# AfternoonCape_RevA2_ADImux.net
KiCad netlist of a schematic drawn in Altium Designer
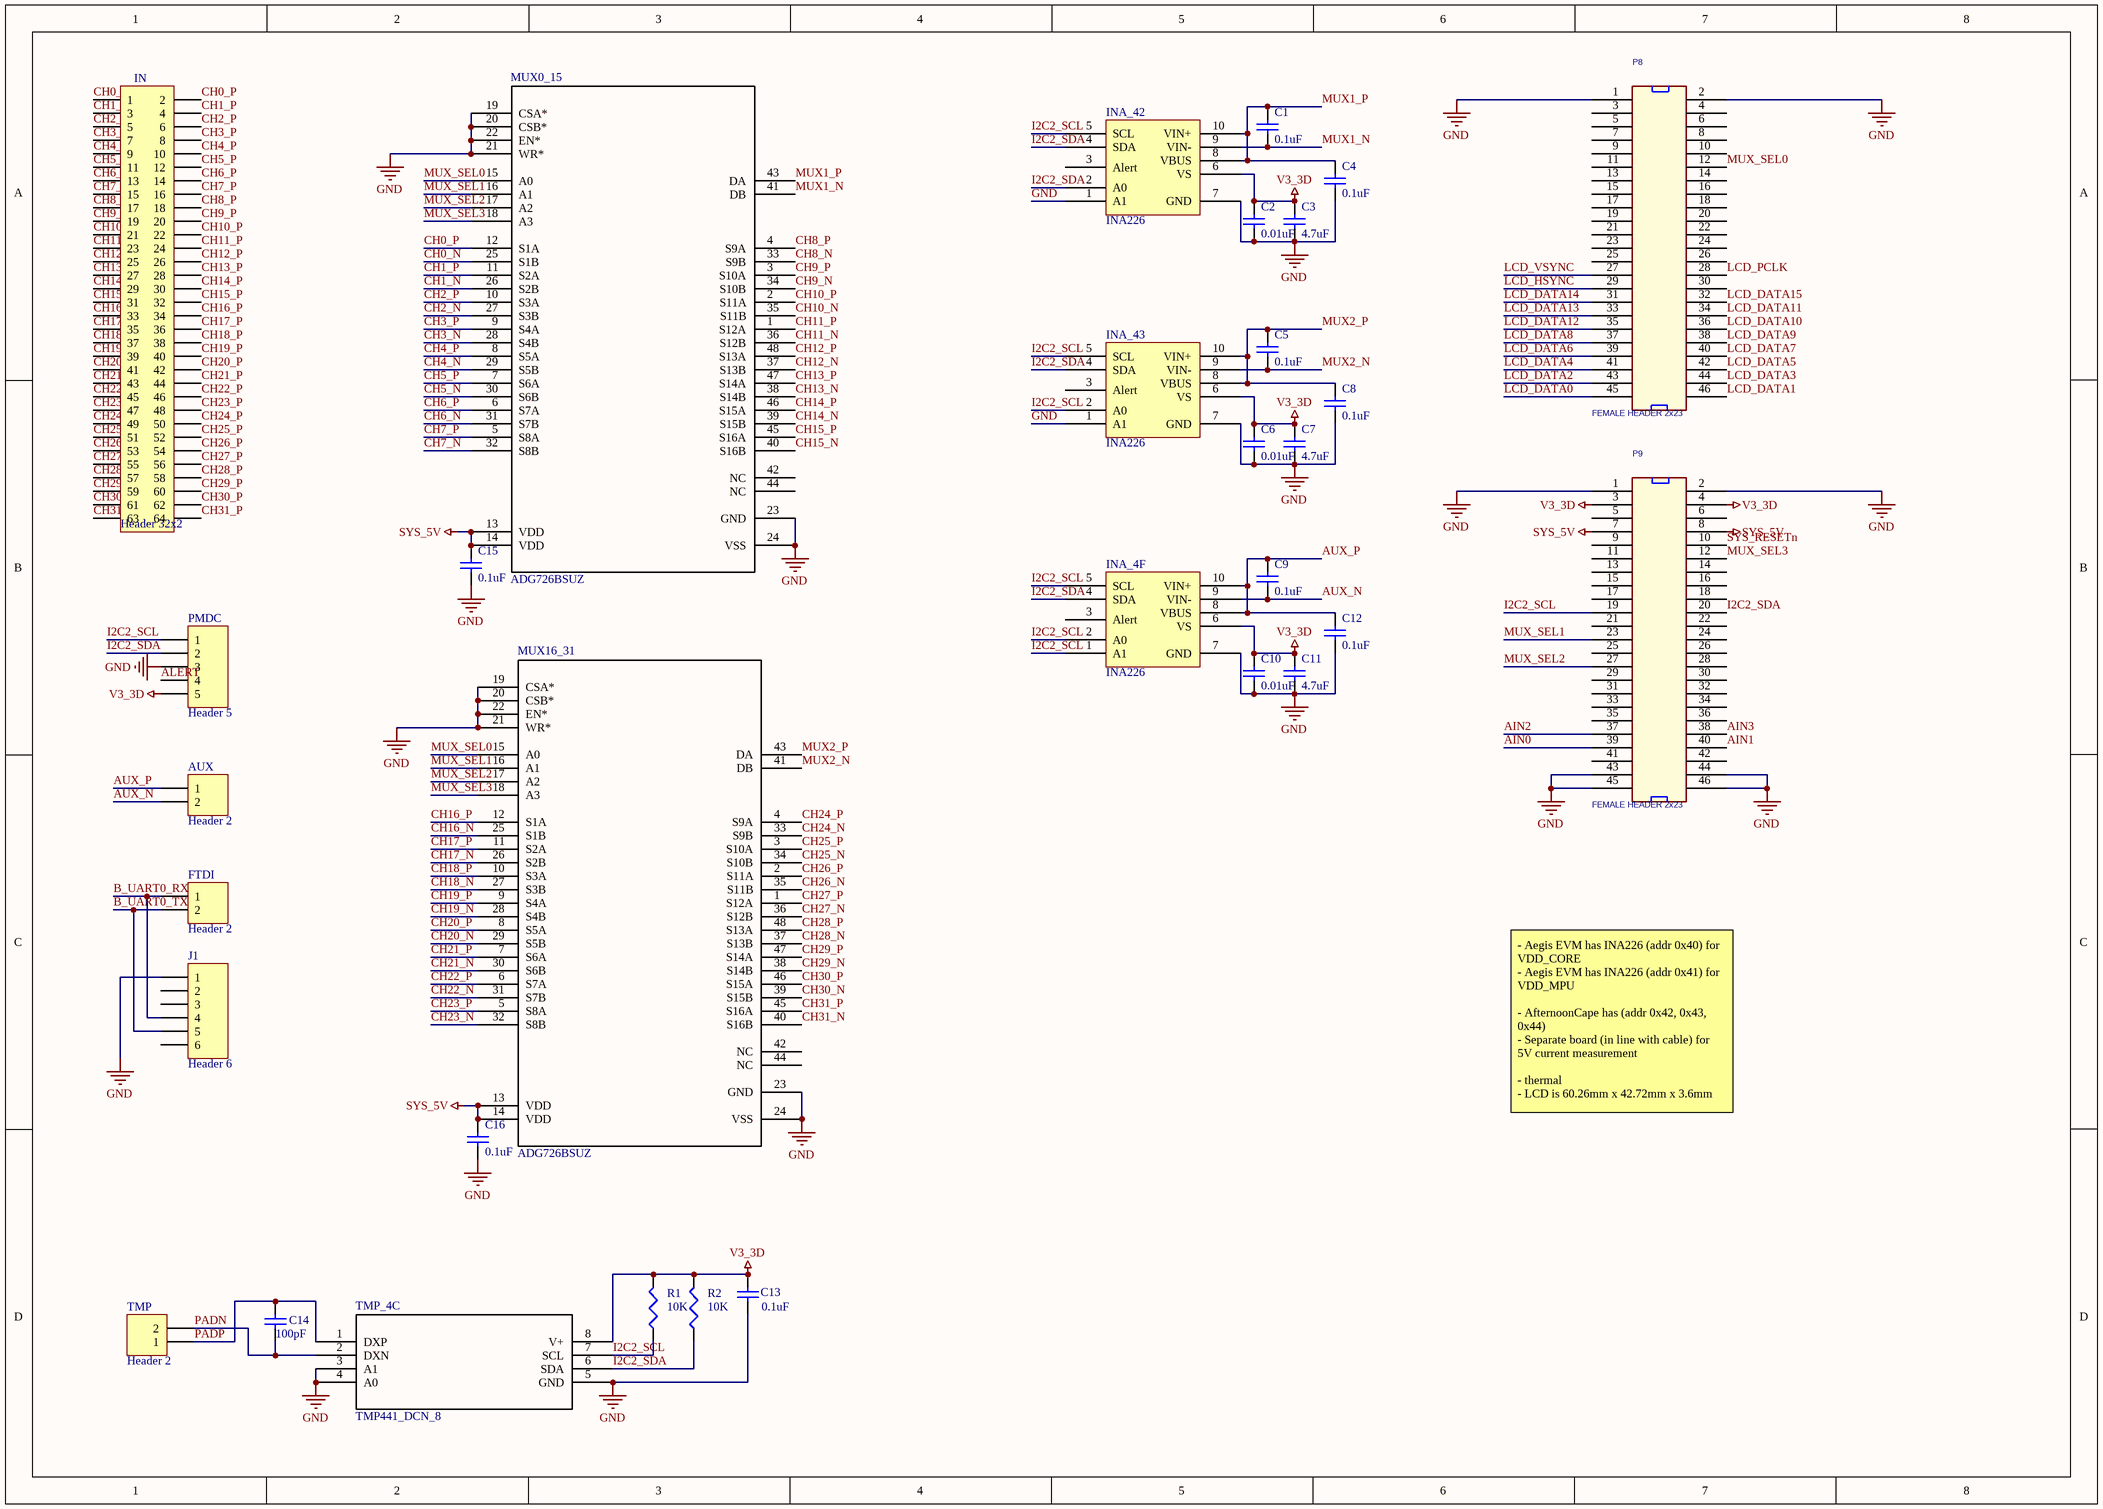
[diagram p0: AfternoonCape_RevA2_ADImux.SchDoc]

(export (version "E")
  (design (tool "Eeschema 10.0.6"))
  (components
    (comp (ref "AUX")
      (value "Header 2")
      (footprint "HDR1X2")
      (description "Header, 2-Pin")
      (fields (field (name "PUBLISHER") "Altium Limited"))
      (libsource (lib "Miscellaneous Connectors") (part "Header 2"))
    )
    (comp (ref "C1")
      (value "0.1uF")
      (footprint "0402")
      (description "Capacitor (Semiconductor SIM Model)")
      (fields (field (name "Comment") "Cap Semi") (field (name "PUBLISHER") "Altium Limited"))
      (libsource (lib "Miscellaneous Devices") (part "Cap Semi"))
    )
    (comp (ref "C2")
      (value "0.01uF")
      (footprint "0402")
      (description "Capacitor (Semiconductor SIM Model)")
      (fields (field (name "Comment") "Cap Semi") (field (name "PUBLISHER") "Altium Limited"))
      (libsource (lib "Miscellaneous Devices") (part "Cap Semi"))
    )
    (comp (ref "C3")
      (value "4.7uF")
      (footprint "0402")
      (description "Capacitor (Semiconductor SIM Model)")
      (fields (field (name "Comment") "Cap Semi") (field (name "PUBLISHER") "Altium Limited"))
      (libsource (lib "Miscellaneous Devices") (part "Cap Semi"))
    )
    (comp (ref "C4")
      (value "0.1uF")
      (footprint "0402")
      (description "Capacitor (Semiconductor SIM Model)")
      (fields (field (name "Comment") "Cap Semi") (field (name "PUBLISHER") "Altium Limited"))
      (libsource (lib "Miscellaneous Devices") (part "Cap Semi"))
    )
    (comp (ref "C5")
      (value "0.1uF")
      (footprint "0402")
      (description "Capacitor (Semiconductor SIM Model)")
      (fields (field (name "Comment") "Cap Semi") (field (name "PUBLISHER") "Altium Limited"))
      (libsource (lib "Miscellaneous Devices") (part "Cap Semi"))
    )
    (comp (ref "C6")
      (value "0.01uF")
      (footprint "0402")
      (description "Capacitor (Semiconductor SIM Model)")
      (fields (field (name "Comment") "Cap Semi") (field (name "PUBLISHER") "Altium Limited"))
      (libsource (lib "Miscellaneous Devices") (part "Cap Semi"))
    )
    (comp (ref "C7")
      (value "4.7uF")
      (footprint "0402")
      (description "Capacitor (Semiconductor SIM Model)")
      (fields (field (name "Comment") "Cap Semi") (field (name "PUBLISHER") "Altium Limited"))
      (libsource (lib "Miscellaneous Devices") (part "Cap Semi"))
    )
    (comp (ref "C8")
      (value "0.1uF")
      (footprint "0402")
      (description "Capacitor (Semiconductor SIM Model)")
      (fields (field (name "Comment") "Cap Semi") (field (name "PUBLISHER") "Altium Limited"))
      (libsource (lib "Miscellaneous Devices") (part "Cap Semi"))
    )
    (comp (ref "C9")
      (value "0.1uF")
      (footprint "0402")
      (description "Capacitor (Semiconductor SIM Model)")
      (fields (field (name "Comment") "Cap Semi") (field (name "PUBLISHER") "Altium Limited"))
      (libsource (lib "Miscellaneous Devices") (part "Cap Semi"))
    )
    (comp (ref "C10")
      (value "0.01uF")
      (footprint "0402")
      (description "Capacitor (Semiconductor SIM Model)")
      (fields (field (name "Comment") "Cap Semi") (field (name "PUBLISHER") "Altium Limited"))
      (libsource (lib "Miscellaneous Devices") (part "Cap Semi"))
    )
    (comp (ref "C11")
      (value "4.7uF")
      (footprint "0402")
      (description "Capacitor (Semiconductor SIM Model)")
      (fields (field (name "Comment") "Cap Semi") (field (name "PUBLISHER") "Altium Limited"))
      (libsource (lib "Miscellaneous Devices") (part "Cap Semi"))
    )
    (comp (ref "C12")
      (value "0.1uF")
      (footprint "0402")
      (description "Capacitor (Semiconductor SIM Model)")
      (fields (field (name "Comment") "Cap Semi") (field (name "PUBLISHER") "Altium Limited"))
      (libsource (lib "Miscellaneous Devices") (part "Cap Semi"))
    )
    (comp (ref "C13")
      (value "0.1uF")
      (footprint "0402")
      (description "Capacitor (Semiconductor SIM Model)")
      (fields (field (name "Comment") "Cap Semi") (field (name "PUBLISHER") "Altium Limited"))
      (libsource (lib "Miscellaneous Devices") (part "Cap Semi"))
    )
    (comp (ref "C14")
      (value "100pF")
      (footprint "0402")
      (description "Capacitor (Semiconductor SIM Model)")
      (fields (field (name "Comment") "Cap Semi") (field (name "PUBLISHER") "Altium Limited"))
      (libsource (lib "Miscellaneous Devices") (part "Cap Semi"))
    )
    (comp (ref "C15")
      (value "0.1uF")
      (footprint "0402")
      (description "Capacitor (Semiconductor SIM Model)")
      (fields (field (name "Comment") "Cap Semi") (field (name "PUBLISHER") "Altium Limited"))
      (libsource (lib "Miscellaneous Devices") (part "Cap Semi"))
    )
    (comp (ref "C16")
      (value "0.1uF")
      (footprint "0402")
      (description "Capacitor (Semiconductor SIM Model)")
      (fields (field (name "Comment") "Cap Semi") (field (name "PUBLISHER") "Altium Limited"))
      (libsource (lib "Miscellaneous Devices") (part "Cap Semi"))
    )
    (comp (ref "FTDI")
      (value "Header 2")
      (footprint "HDR1X2")
      (description "Header, 2-Pin")
      (fields (field (name "PUBLISHER") "Altium Limited"))
      (libsource (lib "Miscellaneous Connectors") (part "Header 2"))
    )
    (comp (ref "IN")
      (value "Header 32x2")
      (footprint "HDR2x32")
      (description "Header, 32-Pin, Dual row")
      (libsource (lib "Miscellaneous Connectors") (part "Header 32x2"))
    )
    (comp (ref "INA_4F") (value "INA226") (footprint "DGS10") (libsource (lib "INA226") (part "INA226")))
    (comp (ref "INA_42") (value "INA226") (footprint "DGS10") (libsource (lib "INA226") (part "INA226")))
    (comp (ref "INA_43") (value "INA226") (footprint "DGS10") (libsource (lib "INA226") (part "INA226")))
    (comp (ref "J1")
      (value "Header 6")
      (footprint "HDR1X6")
      (description "6-pin female header, long legs for FTDI-USB cable")
      (fields (field (name "PUBLISHER") "Altium Limited"))
      (libsource (lib "Miscellaneous Connectors") (part "Header 6"))
    )
    (comp (ref "MUX0_15")
      (value "ADG726BSUZ")
      (footprint "SU_48")
      (description "Imported")
      (libsource (lib "ADG726_ADG732") (part "ADG726BSUZ"))
    )
    (comp (ref "MUX16_31")
      (value "ADG726BSUZ")
      (footprint "SU_48")
      (description "Imported")
      (libsource (lib "ADG726_ADG732") (part "ADG726BSUZ"))
    )
    (comp (ref "P8")
      (value "FEMALE HEADER 2x23")
      (description "CONN HEADER FMAL 46PS.1\" DL GOLD")
      (fields
        (field (name "MANUFACTURER") "Sullins Connector Solutions")
        (field (name "MANUFACTURER PART NUMBER") "PPPC232LFBN-RC")
      )
      (libsource (lib "BEAGLEBONEBLACK_REV A5B") (part "HDR_46_F_2_0.1_0.1"))
    )
    (comp (ref "P9")
      (value "FEMALE HEADER 2x23")
      (description "CONN HEADER FMAL 46PS.1\" DL GOLD")
      (fields
        (field (name "MANUFACTURER") "Sullins Connector Solutions")
        (field (name "MANUFACTURER PART NUMBER") "PPPC232LFBN-RC")
      )
      (libsource (lib "BEAGLEBONEBLACK_REV A5B") (part "HDR_46_F_2_0.1_0.1"))
    )
    (comp (ref "PMDC")
      (value "Header 5")
      (footprint "HDR1X5")
      (description "Header, 5-Pin")
      (fields (field (name "PUBLISHER") "Altium Limited"))
      (libsource (lib "Miscellaneous Connectors") (part "Header 5"))
    )
    (comp (ref "R1")
      (value "10K")
      (footprint "0402")
      (description "Resistor")
      (fields (field (name "Comment") "Res3") (field (name "PUBLISHER") "Altium Limited"))
      (libsource (lib "Miscellaneous Devices") (part "Res3"))
    )
    (comp (ref "R2")
      (value "10K")
      (footprint "0402")
      (description "Resistor")
      (fields (field (name "Comment") "Res3") (field (name "PUBLISHER") "Altium Limited"))
      (libsource (lib "Miscellaneous Devices") (part "Res3"))
    )
    (comp (ref "TMP")
      (value "Header 2")
      (footprint "HDR1X2")
      (description "Header, 2-Pin")
      (fields (field (name "PUBLISHER") "Altium Limited"))
      (libsource (lib "") (part "Header 2_1"))
    )
    (comp (ref "TMP_4C")
      (value "TMP441_DCN_8")
      (footprint "TMP441:DCN8-L")
      (description "Imported")
      (fields
        (field (name "MANUFACTURER_PART_NUMBER") "tmp441_dcn_8")
        (field (name "GENERIC_PART_NUMBER") "TMP441")
      )
      (libsource (lib "TMP441") (part "TMP441_DCN_8"))
    )
  )
  (nets
    (net (code "1") (name "/AIN0") (class "Default")
      (node (ref "P9") (pin "39") (pinfunction "20_39") (pintype "passive"))
    )
    (net (code "2") (name "/AIN1") (class "Default")
      (node (ref "P9") (pin "40") (pinfunction "45_40") (pintype "passive"))
    )
    (net (code "3") (name "/AIN2") (class "Default")
      (node (ref "P9") (pin "37") (pinfunction "19_37") (pintype "passive"))
    )
    (net (code "4") (name "/AIN3") (class "Default")
      (node (ref "P9") (pin "38") (pinfunction "44_38") (pintype "passive"))
    )
    (net (code "5") (name "/ALERT") (class "Default")
      (node (ref "PMDC") (pin "4") (pinfunction "4_4") (pintype "passive"))
    )
    (net (code "6") (name "/AUX_N") (class "Default")
      (node (ref "AUX") (pin "2") (pinfunction "2_2") (pintype "passive"))
      (node (ref "C9") (pin "1") (pinfunction "1_1") (pintype "passive"))
      (node (ref "INA_4F") (pin "9") (pinfunction "VIN-_9") (pintype "passive"))
    )
    (net (code "7") (name "/AUX_P") (class "Default")
      (node (ref "AUX") (pin "1") (pinfunction "1_1") (pintype "passive"))
      (node (ref "C12") (pin "2") (pinfunction "2_2") (pintype "passive"))
      (node (ref "C9") (pin "2") (pinfunction "2_2") (pintype "passive"))
      (node (ref "INA_4F") (pin "10") (pinfunction "VIN+_10") (pintype "passive"))
      (node (ref "INA_4F") (pin "8") (pinfunction "VBUS_8") (pintype "passive"))
    )
    (net (code "8") (name "/B_UART0_RX") (class "Default")
      (node (ref "FTDI") (pin "1") (pinfunction "1_1") (pintype "passive"))
      (node (ref "J1") (pin "4") (pinfunction "4_4") (pintype "passive"))
    )
    (net (code "9") (name "/B_UART0_TX") (class "Default")
      (node (ref "FTDI") (pin "2") (pinfunction "2_2") (pintype "passive"))
      (node (ref "J1") (pin "5") (pinfunction "5_5") (pintype "passive"))
    )
    (net (code "10") (name "/CH0_N") (class "Default")
      (node (ref "IN") (pin "1") (pinfunction "1_1") (pintype "passive"))
      (node (ref "MUX0_15") (pin "25") (pinfunction "S1B_25") (pintype "passive"))
    )
    (net (code "11") (name "/CH0_P") (class "Default")
      (node (ref "IN") (pin "2") (pinfunction "2_2") (pintype "passive"))
      (node (ref "MUX0_15") (pin "12") (pinfunction "S1A_12") (pintype "passive"))
    )
    (net (code "12") (name "/CH1_N") (class "Default")
      (node (ref "IN") (pin "3") (pinfunction "3_3") (pintype "passive"))
      (node (ref "MUX0_15") (pin "26") (pinfunction "S2B_26") (pintype "passive"))
    )
    (net (code "13") (name "/CH1_P") (class "Default")
      (node (ref "IN") (pin "4") (pinfunction "4_4") (pintype "passive"))
      (node (ref "MUX0_15") (pin "11") (pinfunction "S2A_11") (pintype "passive"))
    )
    (net (code "14") (name "/CH2_N") (class "Default")
      (node (ref "IN") (pin "5") (pinfunction "5_5") (pintype "passive"))
      (node (ref "MUX0_15") (pin "27") (pinfunction "S3B_27") (pintype "passive"))
    )
    (net (code "15") (name "/CH2_P") (class "Default")
      (node (ref "IN") (pin "6") (pinfunction "6_6") (pintype "passive"))
      (node (ref "MUX0_15") (pin "10") (pinfunction "S3A_10") (pintype "passive"))
    )
    (net (code "16") (name "/CH3_N") (class "Default")
      (node (ref "IN") (pin "7") (pinfunction "7_7") (pintype "passive"))
      (node (ref "MUX0_15") (pin "28") (pinfunction "S4B_28") (pintype "passive"))
    )
    (net (code "17") (name "/CH3_P") (class "Default")
      (node (ref "IN") (pin "8") (pinfunction "8_8") (pintype "passive"))
      (node (ref "MUX0_15") (pin "9") (pinfunction "S4A_9") (pintype "passive"))
    )
    (net (code "18") (name "/CH4_N") (class "Default")
      (node (ref "IN") (pin "9") (pinfunction "9_9") (pintype "passive"))
      (node (ref "MUX0_15") (pin "29") (pinfunction "S5B_29") (pintype "passive"))
    )
    (net (code "19") (name "/CH4_P") (class "Default")
      (node (ref "IN") (pin "10") (pinfunction "10_10") (pintype "passive"))
      (node (ref "MUX0_15") (pin "8") (pinfunction "S5A_8") (pintype "passive"))
    )
    (net (code "20") (name "/CH5_N") (class "Default")
      (node (ref "IN") (pin "11") (pinfunction "11_11") (pintype "passive"))
      (node (ref "MUX0_15") (pin "30") (pinfunction "S6B_30") (pintype "passive"))
    )
    (net (code "21") (name "/CH5_P") (class "Default")
      (node (ref "IN") (pin "12") (pinfunction "12_12") (pintype "passive"))
      (node (ref "MUX0_15") (pin "7") (pinfunction "S6A_7") (pintype "passive"))
    )
    (net (code "22") (name "/CH6_N") (class "Default")
      (node (ref "IN") (pin "13") (pinfunction "13_13") (pintype "passive"))
      (node (ref "MUX0_15") (pin "31") (pinfunction "S7B_31") (pintype "passive"))
    )
    (net (code "23") (name "/CH6_P") (class "Default")
      (node (ref "IN") (pin "14") (pinfunction "14_14") (pintype "passive"))
      (node (ref "MUX0_15") (pin "6") (pinfunction "S7A_6") (pintype "passive"))
    )
    (net (code "24") (name "/CH7_N") (class "Default")
      (node (ref "IN") (pin "15") (pinfunction "15_15") (pintype "passive"))
      (node (ref "MUX0_15") (pin "32") (pinfunction "S8B_32") (pintype "passive"))
    )
    (net (code "25") (name "/CH7_P") (class "Default")
      (node (ref "IN") (pin "16") (pinfunction "16_16") (pintype "passive"))
      (node (ref "MUX0_15") (pin "5") (pinfunction "S8A_5") (pintype "passive"))
    )
    (net (code "26") (name "/CH8_N") (class "Default")
      (node (ref "IN") (pin "17") (pinfunction "17_17") (pintype "passive"))
      (node (ref "MUX0_15") (pin "33") (pinfunction "S9B_33") (pintype "passive"))
    )
    (net (code "27") (name "/CH8_P") (class "Default")
      (node (ref "IN") (pin "18") (pinfunction "18_18") (pintype "passive"))
      (node (ref "MUX0_15") (pin "4") (pinfunction "S9A_4") (pintype "passive"))
    )
    (net (code "28") (name "/CH9_N") (class "Default")
      (node (ref "IN") (pin "19") (pinfunction "19_19") (pintype "passive"))
      (node (ref "MUX0_15") (pin "34") (pinfunction "S10B_34") (pintype "passive"))
    )
    (net (code "29") (name "/CH9_P") (class "Default")
      (node (ref "IN") (pin "20") (pinfunction "20_20") (pintype "passive"))
      (node (ref "MUX0_15") (pin "3") (pinfunction "S10A_3") (pintype "passive"))
    )
    (net (code "30") (name "/CH10_N") (class "Default")
      (node (ref "IN") (pin "21") (pinfunction "21_21") (pintype "passive"))
      (node (ref "MUX0_15") (pin "35") (pinfunction "S11B_35") (pintype "passive"))
    )
    (net (code "31") (name "/CH10_P") (class "Default")
      (node (ref "IN") (pin "22") (pinfunction "22_22") (pintype "passive"))
      (node (ref "MUX0_15") (pin "2") (pinfunction "S11A_2") (pintype "passive"))
    )
    (net (code "32") (name "/CH11_N") (class "Default")
      (node (ref "IN") (pin "23") (pinfunction "23_23") (pintype "passive"))
      (node (ref "MUX0_15") (pin "36") (pinfunction "S12B_36") (pintype "passive"))
    )
    (net (code "33") (name "/CH11_P") (class "Default")
      (node (ref "IN") (pin "24") (pinfunction "24_24") (pintype "passive"))
      (node (ref "MUX0_15") (pin "1") (pinfunction "S12A_1") (pintype "passive"))
    )
    (net (code "34") (name "/CH12_N") (class "Default")
      (node (ref "IN") (pin "25") (pinfunction "25_25") (pintype "passive"))
      (node (ref "MUX0_15") (pin "37") (pinfunction "S13B_37") (pintype "passive"))
    )
    (net (code "35") (name "/CH12_P") (class "Default")
      (node (ref "IN") (pin "26") (pinfunction "26_26") (pintype "passive"))
      (node (ref "MUX0_15") (pin "48") (pinfunction "S13A_48") (pintype "passive"))
    )
    (net (code "36") (name "/CH13_N") (class "Default")
      (node (ref "IN") (pin "27") (pinfunction "27_27") (pintype "passive"))
      (node (ref "MUX0_15") (pin "38") (pinfunction "S14B_38") (pintype "passive"))
    )
    (net (code "37") (name "/CH13_P") (class "Default")
      (node (ref "IN") (pin "28") (pinfunction "28_28") (pintype "passive"))
      (node (ref "MUX0_15") (pin "47") (pinfunction "S14A_47") (pintype "passive"))
    )
    (net (code "38") (name "/CH14_N") (class "Default")
      (node (ref "IN") (pin "29") (pinfunction "29_29") (pintype "passive"))
      (node (ref "MUX0_15") (pin "39") (pinfunction "S15B_39") (pintype "passive"))
    )
    (net (code "39") (name "/CH14_P") (class "Default")
      (node (ref "IN") (pin "30") (pinfunction "30_30") (pintype "passive"))
      (node (ref "MUX0_15") (pin "46") (pinfunction "S15A_46") (pintype "passive"))
    )
    (net (code "40") (name "/CH15_N") (class "Default")
      (node (ref "IN") (pin "31") (pinfunction "31_31") (pintype "passive"))
      (node (ref "MUX0_15") (pin "40") (pinfunction "S16B_40") (pintype "passive"))
    )
    (net (code "41") (name "/CH15_P") (class "Default")
      (node (ref "IN") (pin "32") (pinfunction "32_32") (pintype "passive"))
      (node (ref "MUX0_15") (pin "45") (pinfunction "S16A_45") (pintype "passive"))
    )
    (net (code "42") (name "/CH16_N") (class "Default")
      (node (ref "IN") (pin "33") (pinfunction "33_33") (pintype "passive"))
      (node (ref "MUX16_31") (pin "25") (pinfunction "S1B_25") (pintype "passive"))
    )
    (net (code "43") (name "/CH16_P") (class "Default")
      (node (ref "IN") (pin "34") (pinfunction "34_34") (pintype "passive"))
      (node (ref "MUX16_31") (pin "12") (pinfunction "S1A_12") (pintype "passive"))
    )
    (net (code "44") (name "/CH17_N") (class "Default")
      (node (ref "IN") (pin "35") (pinfunction "35_35") (pintype "passive"))
      (node (ref "MUX16_31") (pin "26") (pinfunction "S2B_26") (pintype "passive"))
    )
    (net (code "45") (name "/CH17_P") (class "Default")
      (node (ref "IN") (pin "36") (pinfunction "36_36") (pintype "passive"))
      (node (ref "MUX16_31") (pin "11") (pinfunction "S2A_11") (pintype "passive"))
    )
    (net (code "46") (name "/CH18_N") (class "Default")
      (node (ref "IN") (pin "37") (pinfunction "37_37") (pintype "passive"))
      (node (ref "MUX16_31") (pin "27") (pinfunction "S3B_27") (pintype "passive"))
    )
    (net (code "47") (name "/CH18_P") (class "Default")
      (node (ref "IN") (pin "38") (pinfunction "38_38") (pintype "passive"))
      (node (ref "MUX16_31") (pin "10") (pinfunction "S3A_10") (pintype "passive"))
    )
    (net (code "48") (name "/CH19_N") (class "Default")
      (node (ref "IN") (pin "39") (pinfunction "39_39") (pintype "passive"))
      (node (ref "MUX16_31") (pin "28") (pinfunction "S4B_28") (pintype "passive"))
    )
    (net (code "49") (name "/CH19_P") (class "Default")
      (node (ref "IN") (pin "40") (pinfunction "40_40") (pintype "passive"))
      (node (ref "MUX16_31") (pin "9") (pinfunction "S4A_9") (pintype "passive"))
    )
    (net (code "50") (name "/CH20_N") (class "Default")
      (node (ref "IN") (pin "41") (pinfunction "41_41") (pintype "passive"))
      (node (ref "MUX16_31") (pin "29") (pinfunction "S5B_29") (pintype "passive"))
    )
    (net (code "51") (name "/CH20_P") (class "Default")
      (node (ref "IN") (pin "42") (pinfunction "42_42") (pintype "passive"))
      (node (ref "MUX16_31") (pin "8") (pinfunction "S5A_8") (pintype "passive"))
    )
    (net (code "52") (name "/CH21_N") (class "Default")
      (node (ref "IN") (pin "43") (pinfunction "43_43") (pintype "passive"))
      (node (ref "MUX16_31") (pin "30") (pinfunction "S6B_30") (pintype "passive"))
    )
    (net (code "53") (name "/CH21_P") (class "Default")
      (node (ref "IN") (pin "44") (pinfunction "44_44") (pintype "passive"))
      (node (ref "MUX16_31") (pin "7") (pinfunction "S6A_7") (pintype "passive"))
    )
    (net (code "54") (name "/CH22_N") (class "Default")
      (node (ref "IN") (pin "45") (pinfunction "45_45") (pintype "passive"))
      (node (ref "MUX16_31") (pin "31") (pinfunction "S7B_31") (pintype "passive"))
    )
    (net (code "55") (name "/CH22_P") (class "Default")
      (node (ref "IN") (pin "46") (pinfunction "46_46") (pintype "passive"))
      (node (ref "MUX16_31") (pin "6") (pinfunction "S7A_6") (pintype "passive"))
    )
    (net (code "56") (name "/CH23_N") (class "Default")
      (node (ref "IN") (pin "47") (pinfunction "47_47") (pintype "passive"))
      (node (ref "MUX16_31") (pin "32") (pinfunction "S8B_32") (pintype "passive"))
    )
    (net (code "57") (name "/CH23_P") (class "Default")
      (node (ref "IN") (pin "48") (pinfunction "48_48") (pintype "passive"))
      (node (ref "MUX16_31") (pin "5") (pinfunction "S8A_5") (pintype "passive"))
    )
    (net (code "58") (name "/CH24_N") (class "Default")
      (node (ref "IN") (pin "49") (pinfunction "49_49") (pintype "passive"))
      (node (ref "MUX16_31") (pin "33") (pinfunction "S9B_33") (pintype "passive"))
    )
    (net (code "59") (name "/CH24_P") (class "Default")
      (node (ref "IN") (pin "50") (pinfunction "50_50") (pintype "passive"))
      (node (ref "MUX16_31") (pin "4") (pinfunction "S9A_4") (pintype "passive"))
    )
    (net (code "60") (name "/CH25_N") (class "Default")
      (node (ref "IN") (pin "51") (pinfunction "51_51") (pintype "passive"))
      (node (ref "MUX16_31") (pin "34") (pinfunction "S10B_34") (pintype "passive"))
    )
    (net (code "61") (name "/CH25_P") (class "Default")
      (node (ref "IN") (pin "52") (pinfunction "52_52") (pintype "passive"))
      (node (ref "MUX16_31") (pin "3") (pinfunction "S10A_3") (pintype "passive"))
    )
    (net (code "62") (name "/CH26_N") (class "Default")
      (node (ref "IN") (pin "53") (pinfunction "53_53") (pintype "passive"))
      (node (ref "MUX16_31") (pin "35") (pinfunction "S11B_35") (pintype "passive"))
    )
    (net (code "63") (name "/CH26_P") (class "Default")
      (node (ref "IN") (pin "54") (pinfunction "54_54") (pintype "passive"))
      (node (ref "MUX16_31") (pin "2") (pinfunction "S11A_2") (pintype "passive"))
    )
    (net (code "64") (name "/CH27_N") (class "Default")
      (node (ref "IN") (pin "55") (pinfunction "55_55") (pintype "passive"))
      (node (ref "MUX16_31") (pin "36") (pinfunction "S12B_36") (pintype "passive"))
    )
    (net (code "65") (name "/CH27_P") (class "Default")
      (node (ref "IN") (pin "56") (pinfunction "56_56") (pintype "passive"))
      (node (ref "MUX16_31") (pin "1") (pinfunction "S12A_1") (pintype "passive"))
    )
    (net (code "66") (name "/CH28_N") (class "Default")
      (node (ref "IN") (pin "57") (pinfunction "57_57") (pintype "passive"))
      (node (ref "MUX16_31") (pin "37") (pinfunction "S13B_37") (pintype "passive"))
    )
    (net (code "67") (name "/CH28_P") (class "Default")
      (node (ref "IN") (pin "58") (pinfunction "58_58") (pintype "passive"))
      (node (ref "MUX16_31") (pin "48") (pinfunction "S13A_48") (pintype "passive"))
    )
    (net (code "68") (name "/CH29_N") (class "Default")
      (node (ref "IN") (pin "59") (pinfunction "59_59") (pintype "passive"))
      (node (ref "MUX16_31") (pin "38") (pinfunction "S14B_38") (pintype "passive"))
    )
    (net (code "69") (name "/CH29_P") (class "Default")
      (node (ref "IN") (pin "60") (pinfunction "60_60") (pintype "passive"))
      (node (ref "MUX16_31") (pin "47") (pinfunction "S14A_47") (pintype "passive"))
    )
    (net (code "70") (name "/CH30_N") (class "Default")
      (node (ref "IN") (pin "61") (pinfunction "61_61") (pintype "passive"))
      (node (ref "MUX16_31") (pin "39") (pinfunction "S15B_39") (pintype "passive"))
    )
    (net (code "71") (name "/CH30_P") (class "Default")
      (node (ref "IN") (pin "62") (pinfunction "62_62") (pintype "passive"))
      (node (ref "MUX16_31") (pin "46") (pinfunction "S15A_46") (pintype "passive"))
    )
    (net (code "72") (name "/CH31_N") (class "Default")
      (node (ref "IN") (pin "63") (pinfunction "63_63") (pintype "passive"))
      (node (ref "MUX16_31") (pin "40") (pinfunction "S16B_40") (pintype "passive"))
    )
    (net (code "73") (name "/CH31_P") (class "Default")
      (node (ref "IN") (pin "64") (pinfunction "64_64") (pintype "passive"))
      (node (ref "MUX16_31") (pin "45") (pinfunction "S16A_45") (pintype "passive"))
    )
    (net (code "74") (name "/I2C2_SCL") (class "Default")
      (node (ref "INA_42") (pin "5") (pinfunction "SCL_5") (pintype "passive"))
      (node (ref "INA_43") (pin "2") (pinfunction "A0_2") (pintype "passive"))
      (node (ref "INA_43") (pin "5") (pinfunction "SCL_5") (pintype "passive"))
      (node (ref "INA_4F") (pin "1") (pinfunction "A1_1") (pintype "passive"))
      (node (ref "INA_4F") (pin "2") (pinfunction "A0_2") (pintype "passive"))
      (node (ref "INA_4F") (pin "5") (pinfunction "SCL_5") (pintype "passive"))
      (node (ref "P9") (pin "19") (pinfunction "10_19") (pintype "passive"))
      (node (ref "PMDC") (pin "1") (pinfunction "1_1") (pintype "passive"))
      (node (ref "R1") (pin "1") (pinfunction "1_1") (pintype "passive"))
      (node (ref "TMP_4C") (pin "7") (pinfunction "SCL_7") (pintype "passive"))
    )
    (net (code "75") (name "/I2C2_SDA") (class "Default")
      (node (ref "INA_42") (pin "2") (pinfunction "A0_2") (pintype "passive"))
      (node (ref "INA_42") (pin "4") (pinfunction "SDA_4") (pintype "passive"))
      (node (ref "INA_43") (pin "4") (pinfunction "SDA_4") (pintype "passive"))
      (node (ref "INA_4F") (pin "4") (pinfunction "SDA_4") (pintype "passive"))
      (node (ref "P9") (pin "20") (pinfunction "35_20") (pintype "passive"))
      (node (ref "PMDC") (pin "2") (pinfunction "2_2") (pintype "passive"))
      (node (ref "R2") (pin "1") (pinfunction "1_1") (pintype "passive"))
      (node (ref "TMP_4C") (pin "6") (pinfunction "SDA_6") (pintype "passive"))
    )
    (net (code "76") (name "/LCD_DATA0") (class "Default")
      (node (ref "P8") (pin "45") (pinfunction "23_45") (pintype "passive"))
    )
    (net (code "77") (name "/LCD_DATA1") (class "Default")
      (node (ref "P8") (pin "46") (pinfunction "48_46") (pintype "passive"))
    )
    (net (code "78") (name "/LCD_DATA2") (class "Default")
      (node (ref "P8") (pin "43") (pinfunction "22_43") (pintype "passive"))
    )
    (net (code "79") (name "/LCD_DATA3") (class "Default")
      (node (ref "P8") (pin "44") (pinfunction "47_44") (pintype "passive"))
    )
    (net (code "80") (name "/LCD_DATA4") (class "Default")
      (node (ref "P8") (pin "41") (pinfunction "21_41") (pintype "passive"))
    )
    (net (code "81") (name "/LCD_DATA5") (class "Default")
      (node (ref "P8") (pin "42") (pinfunction "46_42") (pintype "passive"))
    )
    (net (code "82") (name "/LCD_DATA6") (class "Default")
      (node (ref "P8") (pin "39") (pinfunction "20_39") (pintype "passive"))
    )
    (net (code "83") (name "/LCD_DATA7") (class "Default")
      (node (ref "P8") (pin "40") (pinfunction "45_40") (pintype "passive"))
    )
    (net (code "84") (name "/LCD_DATA8") (class "Default")
      (node (ref "P8") (pin "37") (pinfunction "19_37") (pintype "passive"))
    )
    (net (code "85") (name "/LCD_DATA9") (class "Default")
      (node (ref "P8") (pin "38") (pinfunction "44_38") (pintype "passive"))
    )
    (net (code "86") (name "/LCD_DATA10") (class "Default")
      (node (ref "P8") (pin "36") (pinfunction "43_36") (pintype "passive"))
    )
    (net (code "87") (name "/LCD_DATA11") (class "Default")
      (node (ref "P8") (pin "34") (pinfunction "42_34") (pintype "passive"))
    )
    (net (code "88") (name "/LCD_DATA12") (class "Default")
      (node (ref "P8") (pin "35") (pinfunction "18_35") (pintype "passive"))
    )
    (net (code "89") (name "/LCD_DATA13") (class "Default")
      (node (ref "P8") (pin "33") (pinfunction "17_33") (pintype "passive"))
    )
    (net (code "90") (name "/LCD_DATA14") (class "Default")
      (node (ref "P8") (pin "31") (pinfunction "16_31") (pintype "passive"))
    )
    (net (code "91") (name "/LCD_DATA15") (class "Default")
      (node (ref "P8") (pin "32") (pinfunction "41_32") (pintype "passive"))
    )
    (net (code "92") (name "/LCD_HSYNC") (class "Default")
      (node (ref "P8") (pin "29") (pinfunction "15_29") (pintype "passive"))
    )
    (net (code "93") (name "/LCD_PCLK") (class "Default")
      (node (ref "P8") (pin "28") (pinfunction "39_28") (pintype "passive"))
    )
    (net (code "94") (name "/LCD_VSYNC") (class "Default")
      (node (ref "P8") (pin "27") (pinfunction "14_27") (pintype "passive"))
    )
    (net (code "95") (name "/MUX1_N") (class "Default")
      (node (ref "C1") (pin "1") (pinfunction "1_1") (pintype "passive"))
      (node (ref "INA_42") (pin "9") (pinfunction "VIN-_9") (pintype "passive"))
      (node (ref "MUX0_15") (pin "41") (pinfunction "DB_41") (pintype "passive"))
    )
    (net (code "96") (name "/MUX1_P") (class "Default")
      (node (ref "C1") (pin "2") (pinfunction "2_2") (pintype "passive"))
      (node (ref "C4") (pin "2") (pinfunction "2_2") (pintype "passive"))
      (node (ref "INA_42") (pin "10") (pinfunction "VIN+_10") (pintype "passive"))
      (node (ref "INA_42") (pin "8") (pinfunction "VBUS_8") (pintype "passive"))
      (node (ref "MUX0_15") (pin "43") (pinfunction "DA_43") (pintype "passive"))
    )
    (net (code "97") (name "/MUX2_N") (class "Default")
      (node (ref "C5") (pin "1") (pinfunction "1_1") (pintype "passive"))
      (node (ref "INA_43") (pin "9") (pinfunction "VIN-_9") (pintype "passive"))
      (node (ref "MUX16_31") (pin "41") (pinfunction "DB_41") (pintype "passive"))
    )
    (net (code "98") (name "/MUX2_P") (class "Default")
      (node (ref "C5") (pin "2") (pinfunction "2_2") (pintype "passive"))
      (node (ref "C8") (pin "2") (pinfunction "2_2") (pintype "passive"))
      (node (ref "INA_43") (pin "10") (pinfunction "VIN+_10") (pintype "passive"))
      (node (ref "INA_43") (pin "8") (pinfunction "VBUS_8") (pintype "passive"))
      (node (ref "MUX16_31") (pin "43") (pinfunction "DA_43") (pintype "passive"))
    )
    (net (code "99") (name "/MUX_SEL0") (class "Default")
      (node (ref "MUX0_15") (pin "15") (pinfunction "A0_15") (pintype "passive"))
      (node (ref "MUX16_31") (pin "15") (pinfunction "A0_15") (pintype "passive"))
      (node (ref "P8") (pin "12") (pinfunction "31_12") (pintype "passive"))
    )
    (net (code "100") (name "/MUX_SEL1") (class "Default")
      (node (ref "MUX0_15") (pin "16") (pinfunction "A1_16") (pintype "passive"))
      (node (ref "MUX16_31") (pin "16") (pinfunction "A1_16") (pintype "passive"))
      (node (ref "P9") (pin "23") (pinfunction "12_23") (pintype "passive"))
    )
    (net (code "101") (name "/MUX_SEL2") (class "Default")
      (node (ref "MUX0_15") (pin "17") (pinfunction "A2_17") (pintype "passive"))
      (node (ref "MUX16_31") (pin "17") (pinfunction "A2_17") (pintype "passive"))
      (node (ref "P9") (pin "27") (pinfunction "14_27") (pintype "passive"))
    )
    (net (code "102") (name "/MUX_SEL3") (class "Default")
      (node (ref "MUX0_15") (pin "18") (pinfunction "A3_18") (pintype "passive"))
      (node (ref "MUX16_31") (pin "18") (pinfunction "A3_18") (pintype "passive"))
      (node (ref "P9") (pin "12") (pinfunction "31_12") (pintype "passive"))
    )
    (net (code "103") (name "/PADN") (class "Default")
      (node (ref "C14") (pin "1") (pinfunction "1_1") (pintype "passive"))
      (node (ref "TMP") (pin "2") (pinfunction "2_2") (pintype "passive"))
      (node (ref "TMP_4C") (pin "2") (pinfunction "DXN_2") (pintype "passive"))
    )
    (net (code "104") (name "/PADP") (class "Default")
      (node (ref "C14") (pin "2") (pinfunction "2_2") (pintype "passive"))
      (node (ref "TMP") (pin "1") (pinfunction "1_1") (pintype "passive"))
      (node (ref "TMP_4C") (pin "1") (pinfunction "DXP_1") (pintype "passive"))
    )
    (net (code "105") (name "/SYS_RESETn") (class "Default")
      (node (ref "P9") (pin "10") (pinfunction "30_10") (pintype "passive"))
    )
    (net (code "106") (name "GND") (class "Default")
      (node (ref "C10") (pin "1") (pinfunction "1_1") (pintype "passive"))
      (node (ref "C11") (pin "1") (pinfunction "1_1") (pintype "passive"))
      (node (ref "C12") (pin "1") (pinfunction "1_1") (pintype "passive"))
      (node (ref "C13") (pin "1") (pinfunction "1_1") (pintype "passive"))
      (node (ref "C15") (pin "1") (pinfunction "1_1") (pintype "passive"))
      (node (ref "C16") (pin "1") (pinfunction "1_1") (pintype "passive"))
      (node (ref "C2") (pin "1") (pinfunction "1_1") (pintype "passive"))
      (node (ref "C3") (pin "1") (pinfunction "1_1") (pintype "passive"))
      (node (ref "C4") (pin "1") (pinfunction "1_1") (pintype "passive"))
      (node (ref "C6") (pin "1") (pinfunction "1_1") (pintype "passive"))
      (node (ref "C7") (pin "1") (pinfunction "1_1") (pintype "passive"))
      (node (ref "C8") (pin "1") (pinfunction "1_1") (pintype "passive"))
      (node (ref "INA_42") (pin "1") (pinfunction "A1_1") (pintype "passive"))
      (node (ref "INA_42") (pin "7") (pinfunction "GND_7") (pintype "passive"))
      (node (ref "INA_43") (pin "1") (pinfunction "A1_1") (pintype "passive"))
      (node (ref "INA_43") (pin "7") (pinfunction "GND_7") (pintype "passive"))
      (node (ref "INA_4F") (pin "7") (pinfunction "GND_7") (pintype "passive"))
      (node (ref "J1") (pin "1") (pinfunction "1_1") (pintype "passive"))
      (node (ref "MUX0_15") (pin "19") (pinfunction "CSA*_19") (pintype "passive"))
      (node (ref "MUX0_15") (pin "20") (pinfunction "CSB*_20") (pintype "passive"))
      (node (ref "MUX0_15") (pin "21") (pinfunction "WR*_21") (pintype "passive"))
      (node (ref "MUX0_15") (pin "22") (pinfunction "EN*_22") (pintype "passive"))
      (node (ref "MUX0_15") (pin "23") (pinfunction "GND_23") (pintype "passive"))
      (node (ref "MUX0_15") (pin "24") (pinfunction "VSS_24") (pintype "power_in"))
      (node (ref "MUX16_31") (pin "19") (pinfunction "CSA*_19") (pintype "passive"))
      (node (ref "MUX16_31") (pin "20") (pinfunction "CSB*_20") (pintype "passive"))
      (node (ref "MUX16_31") (pin "21") (pinfunction "WR*_21") (pintype "passive"))
      (node (ref "MUX16_31") (pin "22") (pinfunction "EN*_22") (pintype "passive"))
      (node (ref "MUX16_31") (pin "23") (pinfunction "GND_23") (pintype "passive"))
      (node (ref "MUX16_31") (pin "24") (pinfunction "VSS_24") (pintype "power_in"))
      (node (ref "P8") (pin "1") (pinfunction "1_1") (pintype "passive"))
      (node (ref "P8") (pin "2") (pinfunction "26_2") (pintype "passive"))
      (node (ref "P9") (pin "1") (pinfunction "1_1") (pintype "passive"))
      (node (ref "P9") (pin "2") (pinfunction "26_2") (pintype "passive"))
      (node (ref "P9") (pin "43") (pinfunction "22_43") (pintype "passive"))
      (node (ref "P9") (pin "44") (pinfunction "47_44") (pintype "passive"))
      (node (ref "P9") (pin "45") (pinfunction "23_45") (pintype "passive"))
      (node (ref "P9") (pin "46") (pinfunction "48_46") (pintype "passive"))
      (node (ref "PMDC") (pin "3") (pinfunction "3_3") (pintype "passive"))
      (node (ref "TMP_4C") (pin "3") (pinfunction "A1_3") (pintype "passive"))
      (node (ref "TMP_4C") (pin "4") (pinfunction "A0_4") (pintype "passive"))
      (node (ref "TMP_4C") (pin "5") (pinfunction "GND_5") (pintype "power_in"))
    )
    (net (code "107") (name "SYS_5V") (class "Default")
      (node (ref "C15") (pin "2") (pinfunction "2_2") (pintype "passive"))
      (node (ref "C16") (pin "2") (pinfunction "2_2") (pintype "passive"))
      (node (ref "MUX0_15") (pin "13") (pinfunction "VDD_13") (pintype "power_in"))
      (node (ref "MUX0_15") (pin "14") (pinfunction "VDD_14") (pintype "power_in"))
      (node (ref "MUX16_31") (pin "13") (pinfunction "VDD_13") (pintype "power_in"))
      (node (ref "MUX16_31") (pin "14") (pinfunction "VDD_14") (pintype "power_in"))
      (node (ref "P9") (pin "7") (pinfunction "4_7") (pintype "passive"))
      (node (ref "P9") (pin "8") (pinfunction "29_8") (pintype "passive"))
    )
    (net (code "108") (name "V3_3D") (class "Default")
      (node (ref "C10") (pin "2") (pinfunction "2_2") (pintype "passive"))
      (node (ref "C11") (pin "2") (pinfunction "2_2") (pintype "passive"))
      (node (ref "C13") (pin "2") (pinfunction "2_2") (pintype "passive"))
      (node (ref "C2") (pin "2") (pinfunction "2_2") (pintype "passive"))
      (node (ref "C3") (pin "2") (pinfunction "2_2") (pintype "passive"))
      (node (ref "C6") (pin "2") (pinfunction "2_2") (pintype "passive"))
      (node (ref "C7") (pin "2") (pinfunction "2_2") (pintype "passive"))
      (node (ref "INA_42") (pin "6") (pinfunction "VS_6") (pintype "passive"))
      (node (ref "INA_43") (pin "6") (pinfunction "VS_6") (pintype "passive"))
      (node (ref "INA_4F") (pin "6") (pinfunction "VS_6") (pintype "passive"))
      (node (ref "P9") (pin "3") (pinfunction "2_3") (pintype "passive"))
      (node (ref "P9") (pin "4") (pinfunction "27_4") (pintype "passive"))
      (node (ref "PMDC") (pin "5") (pinfunction "5_5") (pintype "passive"))
      (node (ref "R1") (pin "2") (pinfunction "2_2") (pintype "passive"))
      (node (ref "R2") (pin "2") (pinfunction "2_2") (pintype "passive"))
      (node (ref "TMP_4C") (pin "8") (pinfunction "V+_8") (pintype "power_in"))
    )
    (net (code "109") (name "unconnected-(INA_4F-Alert-Pad3)") (class "Default")
      (node (ref "INA_4F") (pin "3") (pinfunction "Alert_3") (pintype "passive"))
    )
    (net (code "110") (name "unconnected-(INA_42-Alert-Pad3)") (class "Default")
      (node (ref "INA_42") (pin "3") (pinfunction "Alert_3") (pintype "passive"))
    )
    (net (code "111") (name "unconnected-(INA_43-Alert-Pad3)") (class "Default")
      (node (ref "INA_43") (pin "3") (pinfunction "Alert_3") (pintype "passive"))
    )
    (net (code "112") (name "unconnected-(J1-Pad2)") (class "Default")
      (node (ref "J1") (pin "2") (pinfunction "2_2") (pintype "passive"))
    )
    (net (code "113") (name "unconnected-(J1-Pad3)") (class "Default")
      (node (ref "J1") (pin "3") (pinfunction "3_3") (pintype "passive"))
    )
    (net (code "114") (name "unconnected-(J1-Pad6)") (class "Default")
      (node (ref "J1") (pin "6") (pinfunction "6_6") (pintype "passive"))
    )
    (net (code "115") (name "unconnected-(MUX0_15-NC-Pad42)") (class "Default")
      (node (ref "MUX0_15") (pin "42") (pinfunction "NC_42") (pintype "passive"))
    )
    (net (code "116") (name "unconnected-(MUX0_15-NC-Pad44)") (class "Default")
      (node (ref "MUX0_15") (pin "44") (pinfunction "NC_44") (pintype "passive"))
    )
    (net (code "117") (name "unconnected-(MUX16_31-NC-Pad42)") (class "Default")
      (node (ref "MUX16_31") (pin "42") (pinfunction "NC_42") (pintype "passive"))
    )
    (net (code "118") (name "unconnected-(MUX16_31-NC-Pad44)") (class "Default")
      (node (ref "MUX16_31") (pin "44") (pinfunction "NC_44") (pintype "passive"))
    )
    (net (code "119") (name "unconnected-(P8-2-Pad3)") (class "Default")
      (node (ref "P8") (pin "3") (pinfunction "2_3") (pintype "passive"))
    )
    (net (code "120") (name "unconnected-(P8-3-Pad5)") (class "Default")
      (node (ref "P8") (pin "5") (pinfunction "3_5") (pintype "passive"))
    )
    (net (code "121") (name "unconnected-(P8-4-Pad7)") (class "Default")
      (node (ref "P8") (pin "7") (pinfunction "4_7") (pintype "passive"))
    )
    (net (code "122") (name "unconnected-(P8-5-Pad9)") (class "Default")
      (node (ref "P8") (pin "9") (pinfunction "5_9") (pintype "passive"))
    )
    (net (code "123") (name "unconnected-(P8-6-Pad11)") (class "Default")
      (node (ref "P8") (pin "11") (pinfunction "6_11") (pintype "passive"))
    )
    (net (code "124") (name "unconnected-(P8-7-Pad13)") (class "Default")
      (node (ref "P8") (pin "13") (pinfunction "7_13") (pintype "passive"))
    )
    (net (code "125") (name "unconnected-(P8-8-Pad15)") (class "Default")
      (node (ref "P8") (pin "15") (pinfunction "8_15") (pintype "passive"))
    )
    (net (code "126") (name "unconnected-(P8-9-Pad17)") (class "Default")
      (node (ref "P8") (pin "17") (pinfunction "9_17") (pintype "passive"))
    )
    (net (code "127") (name "unconnected-(P8-10-Pad19)") (class "Default")
      (node (ref "P8") (pin "19") (pinfunction "10_19") (pintype "passive"))
    )
    (net (code "128") (name "unconnected-(P8-11-Pad21)") (class "Default")
      (node (ref "P8") (pin "21") (pinfunction "11_21") (pintype "passive"))
    )
    (net (code "129") (name "unconnected-(P8-12-Pad23)") (class "Default")
      (node (ref "P8") (pin "23") (pinfunction "12_23") (pintype "passive"))
    )
    (net (code "130") (name "unconnected-(P8-13-Pad25)") (class "Default")
      (node (ref "P8") (pin "25") (pinfunction "13_25") (pintype "passive"))
    )
    (net (code "131") (name "unconnected-(P8-27-Pad4)") (class "Default")
      (node (ref "P8") (pin "4") (pinfunction "27_4") (pintype "passive"))
    )
    (net (code "132") (name "unconnected-(P8-28-Pad6)") (class "Default")
      (node (ref "P8") (pin "6") (pinfunction "28_6") (pintype "passive"))
    )
    (net (code "133") (name "unconnected-(P8-29-Pad8)") (class "Default")
      (node (ref "P8") (pin "8") (pinfunction "29_8") (pintype "passive"))
    )
    (net (code "134") (name "unconnected-(P8-30-Pad10)") (class "Default")
      (node (ref "P8") (pin "10") (pinfunction "30_10") (pintype "passive"))
    )
    (net (code "135") (name "unconnected-(P8-32-Pad14)") (class "Default")
      (node (ref "P8") (pin "14") (pinfunction "32_14") (pintype "passive"))
    )
    (net (code "136") (name "unconnected-(P8-33-Pad16)") (class "Default")
      (node (ref "P8") (pin "16") (pinfunction "33_16") (pintype "passive"))
    )
    (net (code "137") (name "unconnected-(P8-34-Pad18)") (class "Default")
      (node (ref "P8") (pin "18") (pinfunction "34_18") (pintype "passive"))
    )
    (net (code "138") (name "unconnected-(P8-35-Pad20)") (class "Default")
      (node (ref "P8") (pin "20") (pinfunction "35_20") (pintype "passive"))
    )
    (net (code "139") (name "unconnected-(P8-36-Pad22)") (class "Default")
      (node (ref "P8") (pin "22") (pinfunction "36_22") (pintype "passive"))
    )
    (net (code "140") (name "unconnected-(P8-37-Pad24)") (class "Default")
      (node (ref "P8") (pin "24") (pinfunction "37_24") (pintype "passive"))
    )
    (net (code "141") (name "unconnected-(P8-38-Pad26)") (class "Default")
      (node (ref "P8") (pin "26") (pinfunction "38_26") (pintype "passive"))
    )
    (net (code "142") (name "unconnected-(P8-40-Pad30)") (class "Default")
      (node (ref "P8") (pin "30") (pinfunction "40_30") (pintype "passive"))
    )
    (net (code "143") (name "unconnected-(P9-3-Pad5)") (class "Default")
      (node (ref "P9") (pin "5") (pinfunction "3_5") (pintype "passive"))
    )
    (net (code "144") (name "unconnected-(P9-5-Pad9)") (class "Default")
      (node (ref "P9") (pin "9") (pinfunction "5_9") (pintype "passive"))
    )
    (net (code "145") (name "unconnected-(P9-6-Pad11)") (class "Default")
      (node (ref "P9") (pin "11") (pinfunction "6_11") (pintype "passive"))
    )
    (net (code "146") (name "unconnected-(P9-7-Pad13)") (class "Default")
      (node (ref "P9") (pin "13") (pinfunction "7_13") (pintype "passive"))
    )
    (net (code "147") (name "unconnected-(P9-8-Pad15)") (class "Default")
      (node (ref "P9") (pin "15") (pinfunction "8_15") (pintype "passive"))
    )
    (net (code "148") (name "unconnected-(P9-9-Pad17)") (class "Default")
      (node (ref "P9") (pin "17") (pinfunction "9_17") (pintype "passive"))
    )
    (net (code "149") (name "unconnected-(P9-11-Pad21)") (class "Default")
      (node (ref "P9") (pin "21") (pinfunction "11_21") (pintype "passive"))
    )
    (net (code "150") (name "unconnected-(P9-13-Pad25)") (class "Default")
      (node (ref "P9") (pin "25") (pinfunction "13_25") (pintype "passive"))
    )
    (net (code "151") (name "unconnected-(P9-15-Pad29)") (class "Default")
      (node (ref "P9") (pin "29") (pinfunction "15_29") (pintype "passive"))
    )
    (net (code "152") (name "unconnected-(P9-16-Pad31)") (class "Default")
      (node (ref "P9") (pin "31") (pinfunction "16_31") (pintype "passive"))
    )
    (net (code "153") (name "unconnected-(P9-17-Pad33)") (class "Default")
      (node (ref "P9") (pin "33") (pinfunction "17_33") (pintype "passive"))
    )
    (net (code "154") (name "unconnected-(P9-18-Pad35)") (class "Default")
      (node (ref "P9") (pin "35") (pinfunction "18_35") (pintype "passive"))
    )
    (net (code "155") (name "unconnected-(P9-21-Pad41)") (class "Default")
      (node (ref "P9") (pin "41") (pinfunction "21_41") (pintype "passive"))
    )
    (net (code "156") (name "unconnected-(P9-28-Pad6)") (class "Default")
      (node (ref "P9") (pin "6") (pinfunction "28_6") (pintype "passive"))
    )
    (net (code "157") (name "unconnected-(P9-32-Pad14)") (class "Default")
      (node (ref "P9") (pin "14") (pinfunction "32_14") (pintype "passive"))
    )
    (net (code "158") (name "unconnected-(P9-33-Pad16)") (class "Default")
      (node (ref "P9") (pin "16") (pinfunction "33_16") (pintype "passive"))
    )
    (net (code "159") (name "unconnected-(P9-34-Pad18)") (class "Default")
      (node (ref "P9") (pin "18") (pinfunction "34_18") (pintype "passive"))
    )
    (net (code "160") (name "unconnected-(P9-36-Pad22)") (class "Default")
      (node (ref "P9") (pin "22") (pinfunction "36_22") (pintype "passive"))
    )
    (net (code "161") (name "unconnected-(P9-37-Pad24)") (class "Default")
      (node (ref "P9") (pin "24") (pinfunction "37_24") (pintype "passive"))
    )
    (net (code "162") (name "unconnected-(P9-38-Pad26)") (class "Default")
      (node (ref "P9") (pin "26") (pinfunction "38_26") (pintype "passive"))
    )
    (net (code "163") (name "unconnected-(P9-39-Pad28)") (class "Default")
      (node (ref "P9") (pin "28") (pinfunction "39_28") (pintype "passive"))
    )
    (net (code "164") (name "unconnected-(P9-40-Pad30)") (class "Default")
      (node (ref "P9") (pin "30") (pinfunction "40_30") (pintype "passive"))
    )
    (net (code "165") (name "unconnected-(P9-41-Pad32)") (class "Default")
      (node (ref "P9") (pin "32") (pinfunction "41_32") (pintype "passive"))
    )
    (net (code "166") (name "unconnected-(P9-42-Pad34)") (class "Default")
      (node (ref "P9") (pin "34") (pinfunction "42_34") (pintype "passive"))
    )
    (net (code "167") (name "unconnected-(P9-43-Pad36)") (class "Default")
      (node (ref "P9") (pin "36") (pinfunction "43_36") (pintype "passive"))
    )
    (net (code "168") (name "unconnected-(P9-46-Pad42)") (class "Default")
      (node (ref "P9") (pin "42") (pinfunction "46_42") (pintype "passive"))
    )
  )
)
